# mcu.net
KiCad netlist of a schematic drawn in Altium Designer
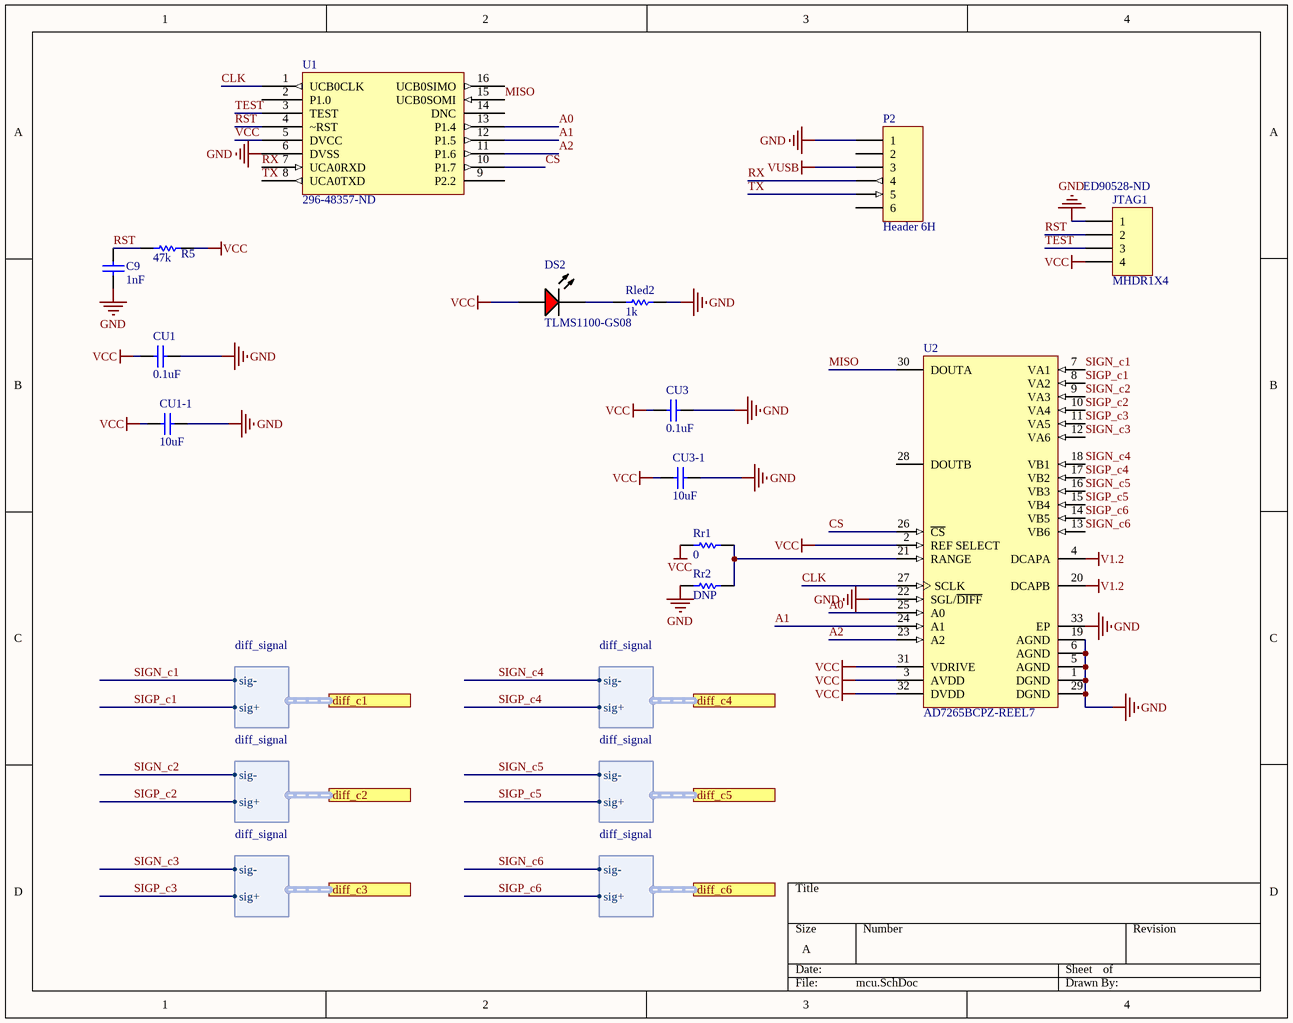
[diagram p0: mcu.SchDoc]

(export (version "E")
  (design (tool "Eeschema 10.0.6"))
  (components
    (comp (ref "C9")
      (value "1nF")
      (footprint "0402")
      (description "Ceramic Capacitor (Surface Mount)")
      (fields (field (name "MANUFACTURER") "Generic Ceramic Chip Cap (TBD)") (field (name "Comment") "Cap"))
      (libsource (lib "maglib") (part "Cap"))
    )
    (comp (ref "CU1")
      (value "0.1uF")
      (footprint "0402")
      (description "Ceramic Capacitor (Surface Mount)")
      (fields (field (name "MANUFACTURER") "Generic Ceramic Chip Cap (TBD)") (field (name "Comment") "Cap"))
      (libsource (lib "maglib") (part "Cap"))
    )
    (comp (ref "CU1-1")
      (value "10uF")
      (footprint "0402")
      (description "Ceramic Capacitor (Surface Mount)")
      (fields (field (name "MANUFACTURER") "Generic Ceramic Chip Cap (TBD)") (field (name "Comment") "Cap"))
      (libsource (lib "maglib") (part "Cap"))
    )
    (comp (ref "CU3")
      (value "0.1uF")
      (footprint "0402")
      (description "Ceramic Capacitor (Surface Mount)")
      (fields (field (name "MANUFACTURER") "Generic Ceramic Chip Cap (TBD)") (field (name "Comment") "Cap"))
      (libsource (lib "maglib") (part "Cap"))
    )
    (comp (ref "CU3-1")
      (value "10uF")
      (footprint "0402")
      (description "Ceramic Capacitor (Surface Mount)")
      (fields (field (name "MANUFACTURER") "Generic Ceramic Chip Cap (TBD)") (field (name "Comment") "Cap"))
      (libsource (lib "maglib") (part "Cap"))
    )
    (comp (ref "DS2")
      (value "TLMS1100-GS08")
      (footprint "VISH-TLMX1100_V")
      (description "LED, RED, 2.1 V, -40 to 100 degC, 2-Pin SMD (0603), RoHS, Tape and Reel")
      (fields (field (name "TOLERANCE") "5%"))
      (libsource (lib "Altium Content Vault") (part "LED-RED-AK-2"))
    )
    (comp (ref "JTAG1")
      (value "MHDR1X4")
      (footprint "MHDR1X4")
      (description "Header, 4-Pin")
      (fields
        (field (name "SUPPLIER PART NUMBER 1") "ED90528-ND")
        (field (name "PUBLISHER") "Altium Limited")
      )
      (libsource (lib "Miscellaneous Connectors") (part "MHDR1X4"))
    )
    (comp (ref "P2")
      (value "Header 6H")
      (footprint "HDR1X6H")
      (description "Header, 6-Pin, Right Angle")
      (fields (field (name "PUBLISHER") "Altium Limited"))
      (libsource (lib "Miscellaneous Connectors") (part "Header 6H"))
    )
    (comp (ref "R5")
      (value "47k")
      (footprint "0402")
      (description "Chip Resistor (Surface Mount)")
      (fields (field (name "MANUFACTURER") "Generic Chip Res (TBD)") (field (name "Comment") "Res"))
      (libsource (lib "maglib") (part "Res"))
    )
    (comp (ref "Rled2")
      (value "1k")
      (footprint "0402")
      (description "Chip Resistor (Surface Mount)")
      (fields (field (name "MANUFACTURER") "Generic Chip Res (TBD)") (field (name "Comment") "Res"))
      (libsource (lib "maglib") (part "Res"))
    )
    (comp (ref "Rr1")
      (value "0")
      (footprint "0402")
      (description "Chip Resistor (Surface Mount)")
      (fields (field (name "MANUFACTURER") "Generic Chip Res (TBD)") (field (name "Comment") "Res"))
      (libsource (lib "maglib") (part "Res"))
    )
    (comp (ref "Rr2")
      (value "DNP")
      (footprint "0402")
      (description "Chip Resistor (Surface Mount)")
      (fields (field (name "MANUFACTURER") "Generic Chip Res (TBD)") (field (name "Comment") "Res"))
      (libsource (lib "maglib") (part "Res"))
    )
    (comp (ref "U1")
      (value "MSP430FR2422")
      (footprint "TSOP65P640X120-16N")
      (description "MSP430FR2422 Mixed-Signal Microcontroller")
      (fields (field (name "SUPPLIER PART NUMBER 1") "296-48357-ND"))
      (libsource (lib "maglib") (part "MSP430FR2422"))
    )
    (comp (ref "U2")
      (value "AD7265BCPZ-REEL7")
      (footprint "CP-32-2_M")
      (fields (field (name "GENERIC PART NUMBER") "AD7265") (field (name "MANUFACTURER") "Analog Devices"))
      (libsource (lib "Altium Content Vault") (part "ADI-AD7265-CP-32-2"))
    )
  )
  (nets
    (net (code "2") (name "/A0") (class "Default")
      (node (ref "U1") (pin "13") (pinfunction "P1.4_13") (pintype "output"))
      (node (ref "U2") (pin "25") (pinfunction "A0_25") (pintype "input"))
    )
    (net (code "3") (name "/A1") (class "Default")
      (node (ref "U1") (pin "12") (pinfunction "P1.5_12") (pintype "output"))
      (node (ref "U2") (pin "24") (pinfunction "A1_24") (pintype "input"))
    )
    (net (code "4") (name "/A2") (class "Default")
      (node (ref "U1") (pin "11") (pinfunction "P1.6_11") (pintype "output"))
      (node (ref "U2") (pin "23") (pinfunction "A2_23") (pintype "input"))
    )
    (net (code "5") (name "/CLK") (class "Default")
      (node (ref "U1") (pin "1") (pinfunction "UCB0CLK_1") (pintype "output"))
      (node (ref "U2") (pin "27") (pinfunction "SCLK_27") (pintype "input"))
    )
    (net (code "6") (name "/CS") (class "Default")
      (node (ref "U1") (pin "10") (pinfunction "P1.7_10") (pintype "output"))
      (node (ref "U2") (pin "26") (pinfunction "~{CS}_26") (pintype "input"))
    )
    (net (code "7") (name "/MISO") (class "Default")
      (node (ref "U1") (pin "15") (pinfunction "UCB0SOMI_15") (pintype "input"))
      (node (ref "U2") (pin "30") (pinfunction "DOUTA_30") (pintype "tri_state"))
    )
    (net (code "8") (name "/RST") (class "Default")
      (node (ref "C9") (pin "2") (pinfunction "2_2") (pintype "passive"))
      (node (ref "JTAG1") (pin "2") (pinfunction "2_2") (pintype "passive"))
      (node (ref "R5") (pin "1") (pinfunction "1_1") (pintype "passive"))
      (node (ref "U1") (pin "4") (pinfunction "~RST_4") (pintype "passive"))
    )
    (net (code "9") (name "/RX") (class "Default")
      (node (ref "P2") (pin "4") (pinfunction "4_4") (pintype "output"))
      (node (ref "U1") (pin "7") (pinfunction "UCA0RXD_7") (pintype "input"))
    )
    (net (code "10") (name "/SIGN_c1") (class "Default")
      (node (ref "U2") (pin "7") (pinfunction "VA1_7") (pintype "input"))
    )
    (net (code "11") (name "/SIGN_c2") (class "Default")
      (node (ref "U2") (pin "9") (pinfunction "VA3_9") (pintype "input"))
    )
    (net (code "12") (name "/SIGN_c3") (class "Default")
      (node (ref "U2") (pin "12") (pinfunction "VA6_12") (pintype "input"))
    )
    (net (code "13") (name "/SIGN_c4") (class "Default")
      (node (ref "U2") (pin "18") (pinfunction "VB1_18") (pintype "input"))
    )
    (net (code "14") (name "/SIGN_c5") (class "Default")
      (node (ref "U2") (pin "16") (pinfunction "VB3_16") (pintype "input"))
    )
    (net (code "15") (name "/SIGN_c6") (class "Default")
      (node (ref "U2") (pin "13") (pinfunction "VB6_13") (pintype "input"))
    )
    (net (code "16") (name "/SIGP_c1") (class "Default")
      (node (ref "U2") (pin "8") (pinfunction "VA2_8") (pintype "input"))
    )
    (net (code "17") (name "/SIGP_c2") (class "Default")
      (node (ref "U2") (pin "10") (pinfunction "VA4_10") (pintype "input"))
    )
    (net (code "18") (name "/SIGP_c3") (class "Default")
      (node (ref "U2") (pin "11") (pinfunction "VA5_11") (pintype "input"))
    )
    (net (code "19") (name "/SIGP_c4") (class "Default")
      (node (ref "U2") (pin "17") (pinfunction "VB2_17") (pintype "input"))
    )
    (net (code "20") (name "/SIGP_c5") (class "Default")
      (node (ref "U2") (pin "15") (pinfunction "VB4_15") (pintype "input"))
    )
    (net (code "21") (name "/SIGP_c6") (class "Default")
      (node (ref "U2") (pin "14") (pinfunction "VB5_14") (pintype "input"))
    )
    (net (code "22") (name "/TEST") (class "Default")
      (node (ref "JTAG1") (pin "3") (pinfunction "3_3") (pintype "passive"))
      (node (ref "U1") (pin "3") (pinfunction "TEST_3") (pintype "passive"))
    )
    (net (code "23") (name "/TX") (class "Default")
      (node (ref "P2") (pin "5") (pinfunction "5_5") (pintype "input"))
      (node (ref "U1") (pin "8") (pinfunction "UCA0TXD_8") (pintype "output"))
    )
    (net (code "25") (name "GND") (class "Default")
      (node (ref "C9") (pin "1") (pinfunction "1_1") (pintype "passive"))
      (node (ref "CU1") (pin "1") (pinfunction "1_1") (pintype "passive"))
      (node (ref "CU1-1") (pin "1") (pinfunction "1_1") (pintype "passive"))
      (node (ref "CU3") (pin "1") (pinfunction "1_1") (pintype "passive"))
      (node (ref "CU3-1") (pin "1") (pinfunction "1_1") (pintype "passive"))
      (node (ref "JTAG1") (pin "1") (pinfunction "1_1") (pintype "passive"))
      (node (ref "P2") (pin "1") (pinfunction "1_1") (pintype "passive"))
      (node (ref "Rled2") (pin "2") (pinfunction "2_2") (pintype "passive"))
      (node (ref "Rr2") (pin "1") (pinfunction "1_1") (pintype "passive"))
      (node (ref "U1") (pin "6") (pinfunction "DVSS_6") (pintype "power_in"))
      (node (ref "U2") (pin "1") (pinfunction "DGND_1") (pintype "power_in"))
      (node (ref "U2") (pin "19") (pinfunction "AGND_19") (pintype "power_in"))
      (node (ref "U2") (pin "22") (pinfunction "SGL/~{DIFF}_22") (pintype "input"))
      (node (ref "U2") (pin "29") (pinfunction "DGND_29") (pintype "power_in"))
      (node (ref "U2") (pin "33") (pinfunction "EP_33") (pintype "power_in"))
      (node (ref "U2") (pin "5") (pinfunction "AGND_5") (pintype "power_in"))
      (node (ref "U2") (pin "6") (pinfunction "AGND_6") (pintype "power_in"))
    )
    (net (code "26") (name "Net-(DS2-K)") (class "Default")
      (node (ref "DS2") (pin "2") (pinfunction "K_2") (pintype "passive"))
      (node (ref "Rled2") (pin "1") (pinfunction "1_1") (pintype "passive"))
    )
    (net (code "27") (name "Net-(U2-RANGE)") (class "Default")
      (node (ref "Rr1") (pin "2") (pinfunction "2_2") (pintype "passive"))
      (node (ref "Rr2") (pin "2") (pinfunction "2_2") (pintype "passive"))
      (node (ref "U2") (pin "21") (pinfunction "RANGE_21") (pintype "input"))
    )
    (net (code "28") (name "V1.2") (class "Default")
      (node (ref "U2") (pin "20") (pinfunction "DCAPB_20") (pintype "passive"))
      (node (ref "U2") (pin "4") (pinfunction "DCAPA_4") (pintype "passive"))
    )
    (net (code "29") (name "VCC") (class "Default")
      (node (ref "CU1") (pin "2") (pinfunction "2_2") (pintype "passive"))
      (node (ref "CU1-1") (pin "2") (pinfunction "2_2") (pintype "passive"))
      (node (ref "CU3") (pin "2") (pinfunction "2_2") (pintype "passive"))
      (node (ref "CU3-1") (pin "2") (pinfunction "2_2") (pintype "passive"))
      (node (ref "DS2") (pin "1") (pinfunction "A_1") (pintype "passive"))
      (node (ref "JTAG1") (pin "4") (pinfunction "4_4") (pintype "passive"))
      (node (ref "R5") (pin "2") (pinfunction "2_2") (pintype "passive"))
      (node (ref "Rr1") (pin "1") (pinfunction "1_1") (pintype "passive"))
      (node (ref "U1") (pin "5") (pinfunction "DVCC_5") (pintype "power_in"))
      (node (ref "U2") (pin "2") (pinfunction "REF_SELECT_2") (pintype "input"))
      (node (ref "U2") (pin "3") (pinfunction "AVDD_3") (pintype "power_in"))
      (node (ref "U2") (pin "31") (pinfunction "VDRIVE_31") (pintype "power_in"))
      (node (ref "U2") (pin "32") (pinfunction "DVDD_32") (pintype "power_in"))
    )
    (net (code "30") (name "VUSB") (class "Default")
      (node (ref "P2") (pin "3") (pinfunction "3_3") (pintype "passive"))
    )
    (net (code "31") (name "unconnected-(P2-Pad2)") (class "Default")
      (node (ref "P2") (pin "2") (pinfunction "2_2") (pintype "passive"))
    )
    (net (code "32") (name "unconnected-(P2-Pad6)") (class "Default")
      (node (ref "P2") (pin "6") (pinfunction "6_6") (pintype "passive"))
    )
    (net (code "33") (name "unconnected-(U1-DNC-Pad14)") (class "Default")
      (node (ref "U1") (pin "14") (pinfunction "DNC_14") (pintype "passive"))
    )
    (net (code "34") (name "unconnected-(U1-P1.0-Pad2)") (class "Default")
      (node (ref "U1") (pin "2") (pinfunction "P1.0_2") (pintype "passive"))
    )
    (net (code "35") (name "unconnected-(U1-P2.2-Pad9)") (class "Default")
      (node (ref "U1") (pin "9") (pinfunction "P2.2_9") (pintype "passive"))
    )
    (net (code "36") (name "unconnected-(U1-UCB0SIMO-Pad16)") (class "Default")
      (node (ref "U1") (pin "16") (pinfunction "UCB0SIMO_16") (pintype "output"))
    )
    (net (code "37") (name "unconnected-(U2-DOUTB-Pad28)") (class "Default")
      (node (ref "U2") (pin "28") (pinfunction "DOUTB_28") (pintype "tri_state"))
    )
  )
)
